# Sheet_MB.net
KiCad netlist of a schematic drawn in Altium Designer
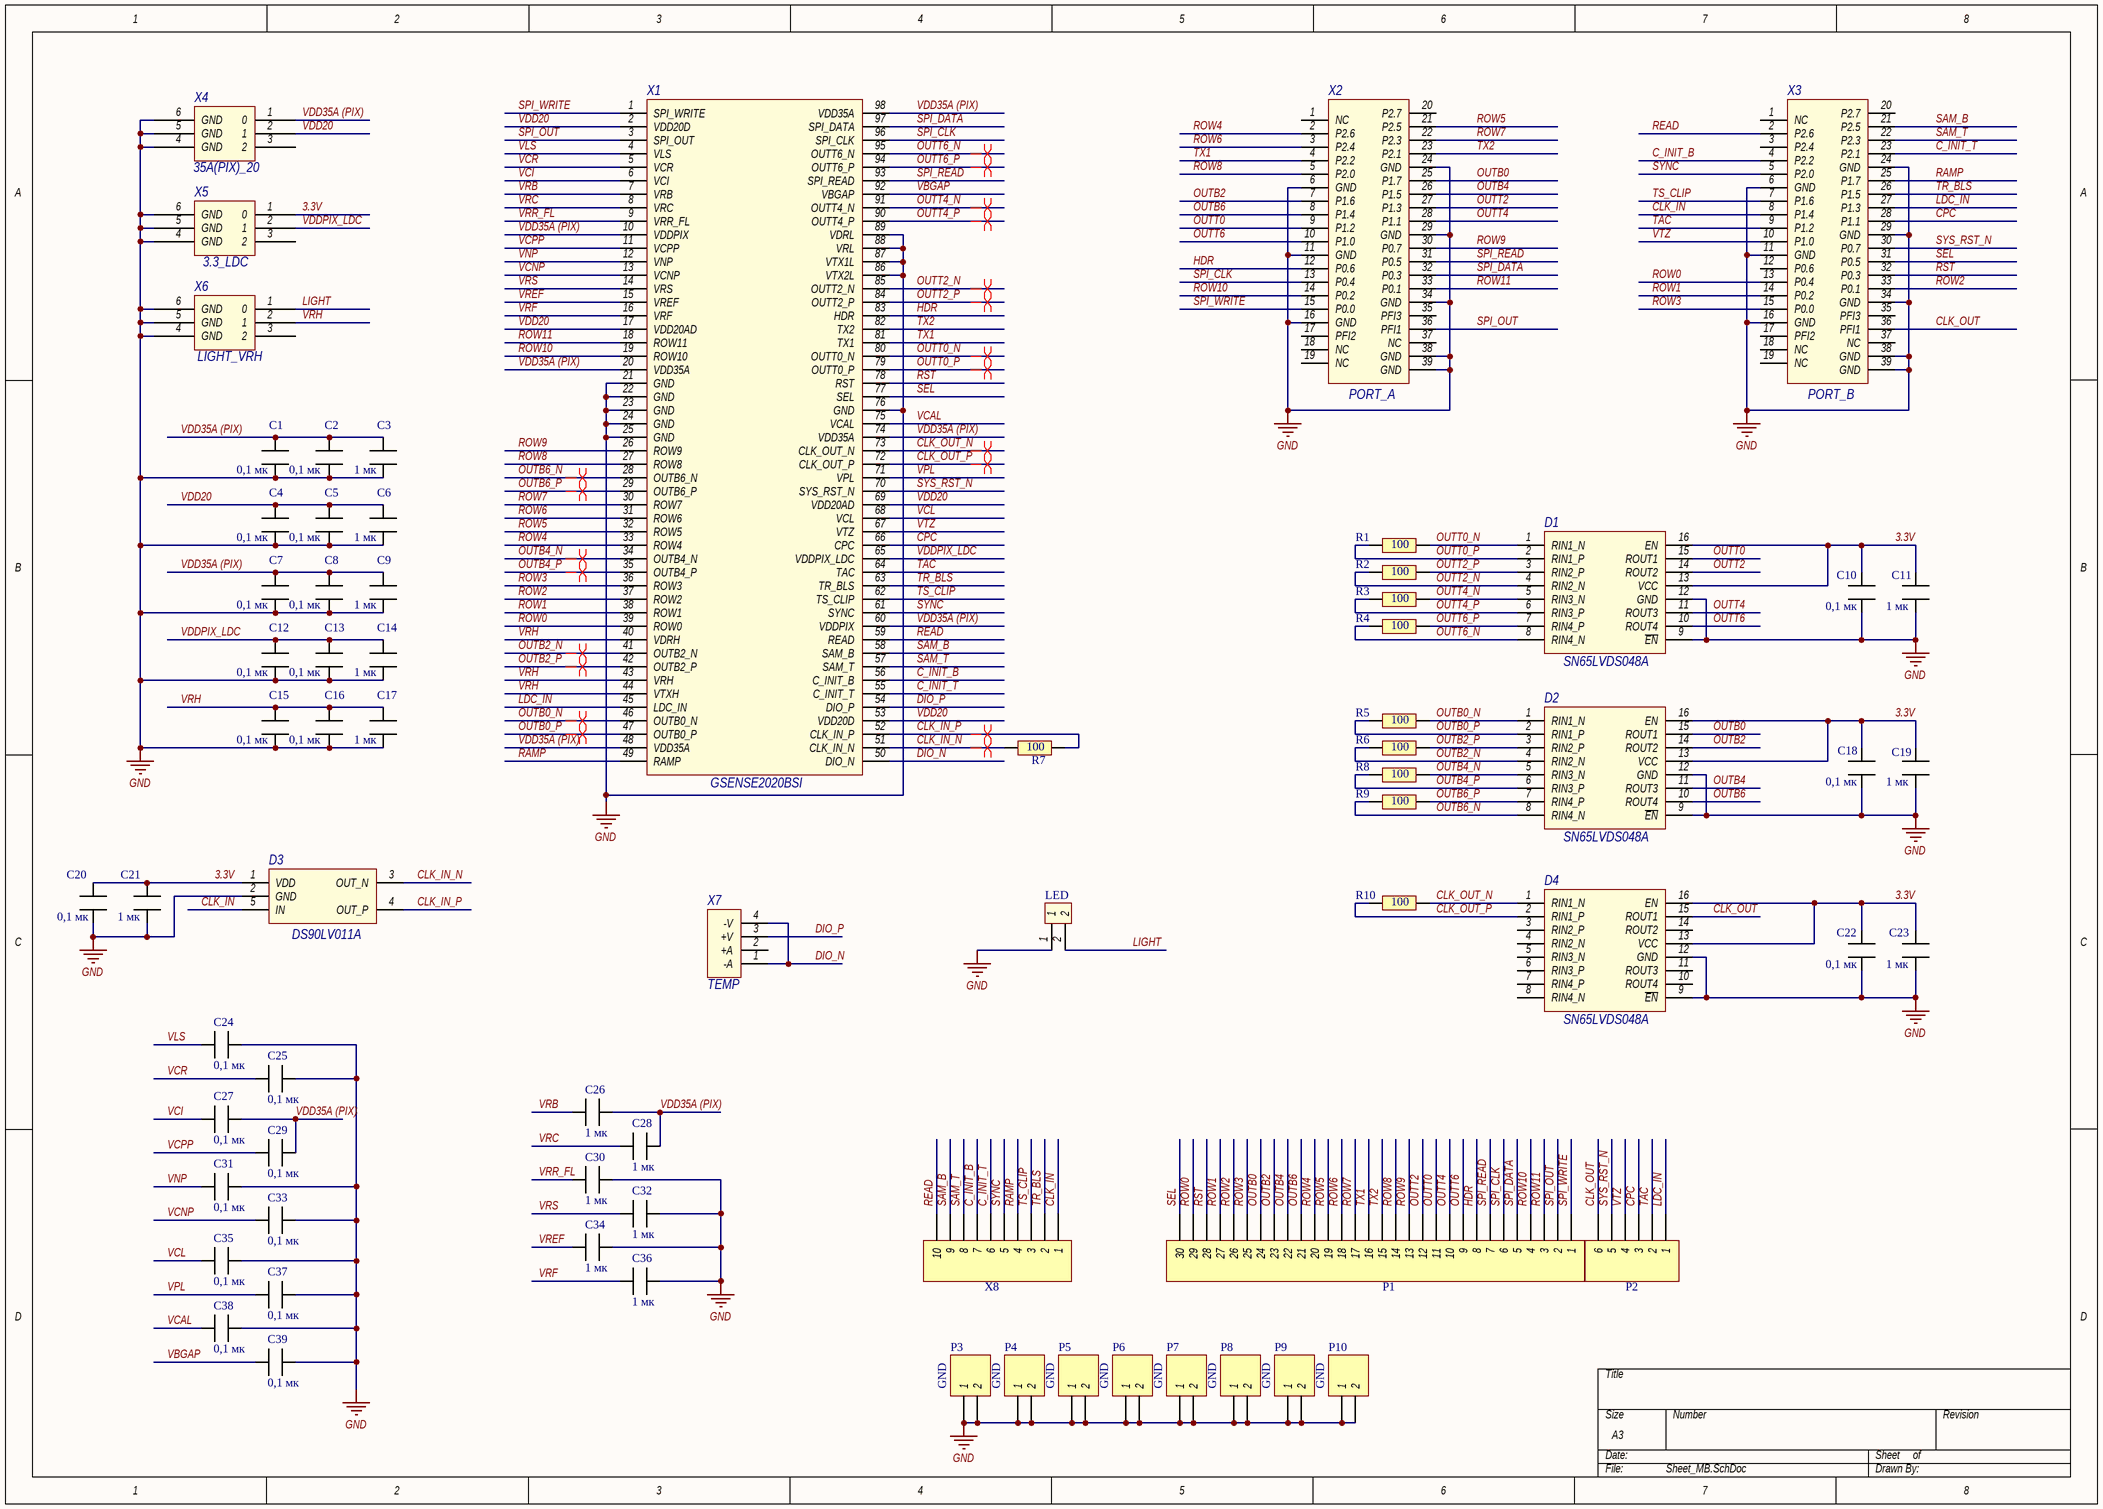
[diagram p0: Sheet_MB.SchDoc]

(export (version "E")
  (design (tool "Eeschema 10.0.6"))
  (components
    (comp (ref "C1") (value "0,1 мк") (footprint "CAP_SMALL") (libsource (lib "Schlib") (part "CAP_SMALL")))
    (comp (ref "C2") (value "0,1 мк") (footprint "CAP_SMALL") (libsource (lib "Schlib") (part "CAP_SMALL")))
    (comp (ref "C3") (value "1 мк") (footprint "CAP_SMALL") (libsource (lib "Schlib") (part "CAP_SMALL")))
    (comp (ref "C4") (value "0,1 мк") (footprint "CAP_SMALL") (libsource (lib "Schlib") (part "CAP_SMALL")))
    (comp (ref "C5") (value "0,1 мк") (footprint "CAP_SMALL") (libsource (lib "Schlib") (part "CAP_SMALL")))
    (comp (ref "C6") (value "1 мк") (footprint "CAP_SMALL") (libsource (lib "Schlib") (part "CAP_SMALL")))
    (comp (ref "C7") (value "0,1 мк") (footprint "CAP_SMALL") (libsource (lib "Schlib") (part "CAP_SMALL")))
    (comp (ref "C8") (value "0,1 мк") (footprint "CAP_SMALL") (libsource (lib "Schlib") (part "CAP_SMALL")))
    (comp (ref "C9") (value "1 мк") (footprint "CAP_SMALL") (libsource (lib "Schlib") (part "CAP_SMALL")))
    (comp (ref "C10") (value "0,1 мк") (footprint "CAP_SMALL") (libsource (lib "Schlib") (part "CAP_SMALL")))
    (comp (ref "C11") (value "1 мк") (footprint "CAP_SMALL") (libsource (lib "Schlib") (part "CAP_SMALL")))
    (comp (ref "C12") (value "0,1 мк") (footprint "CAP_SMALL") (libsource (lib "Schlib") (part "CAP_SMALL")))
    (comp (ref "C13") (value "0,1 мк") (footprint "CAP_SMALL") (libsource (lib "Schlib") (part "CAP_SMALL")))
    (comp (ref "C14") (value "1 мк") (footprint "CAP_SMALL") (libsource (lib "Schlib") (part "CAP_SMALL")))
    (comp (ref "C15") (value "0,1 мк") (footprint "CAP_SMALL") (libsource (lib "Schlib") (part "CAP_SMALL")))
    (comp (ref "C16") (value "0,1 мк") (footprint "CAP_SMALL") (libsource (lib "Schlib") (part "CAP_SMALL")))
    (comp (ref "C17") (value "1 мк") (footprint "CAP_SMALL") (libsource (lib "Schlib") (part "CAP_SMALL")))
    (comp (ref "C18") (value "0,1 мк") (footprint "CAP_SMALL") (libsource (lib "Schlib") (part "CAP_SMALL")))
    (comp (ref "C19") (value "1 мк") (footprint "CAP_SMALL") (libsource (lib "Schlib") (part "CAP_SMALL")))
    (comp (ref "C20") (value "0,1 мк") (footprint "CAP_SMALL") (libsource (lib "Schlib") (part "CAP_SMALL")))
    (comp (ref "C21") (value "1 мк") (footprint "CAP_SMALL") (libsource (lib "Schlib") (part "CAP_SMALL")))
    (comp (ref "C22") (value "0,1 мк") (footprint "CAP_SMALL") (libsource (lib "Schlib") (part "CAP_SMALL")))
    (comp (ref "C23") (value "1 мк") (footprint "CAP_SMALL") (libsource (lib "Schlib") (part "CAP_SMALL")))
    (comp (ref "C24") (value "0,1 мк") (footprint "CAP_SMALL") (libsource (lib "Schlib") (part "CAP_SMALL")))
    (comp (ref "C25") (value "0,1 мк") (footprint "CAP_SMALL") (libsource (lib "Schlib") (part "CAP_SMALL")))
    (comp (ref "C26") (value "1 мк") (footprint "CAP_SMALL") (libsource (lib "Schlib") (part "CAP_SMALL")))
    (comp (ref "C27") (value "0,1 мк") (footprint "CAP_SMALL") (libsource (lib "Schlib") (part "CAP_SMALL")))
    (comp (ref "C28") (value "1 мк") (footprint "CAP_SMALL") (libsource (lib "Schlib") (part "CAP_SMALL")))
    (comp (ref "C29") (value "0,1 мк") (footprint "CAP_SMALL") (libsource (lib "Schlib") (part "CAP_SMALL")))
    (comp (ref "C30") (value "1 мк") (footprint "CAP_SMALL") (libsource (lib "Schlib") (part "CAP_SMALL")))
    (comp (ref "C31") (value "0,1 мк") (footprint "CAP_SMALL") (libsource (lib "Schlib") (part "CAP_SMALL")))
    (comp (ref "C32") (value "1 мк") (footprint "CAP_SMALL") (libsource (lib "Schlib") (part "CAP_SMALL")))
    (comp (ref "C33") (value "0,1 мк") (footprint "CAP_SMALL") (libsource (lib "Schlib") (part "CAP_SMALL")))
    (comp (ref "C34") (value "1 мк") (footprint "CAP_SMALL") (libsource (lib "Schlib") (part "CAP_SMALL")))
    (comp (ref "C35") (value "0,1 мк") (footprint "CAP_SMALL") (libsource (lib "Schlib") (part "CAP_SMALL")))
    (comp (ref "C36") (value "1 мк") (footprint "CAP_SMALL") (libsource (lib "Schlib") (part "CAP_SMALL")))
    (comp (ref "C37") (value "0,1 мк") (footprint "CAP_SMALL") (libsource (lib "Schlib") (part "CAP_SMALL")))
    (comp (ref "C38") (value "0,1 мк") (footprint "CAP_SMALL") (libsource (lib "Schlib") (part "CAP_SMALL")))
    (comp (ref "C39") (value "0,1 мк") (footprint "CAP_SMALL") (libsource (lib "Schlib") (part "CAP_SMALL")))
    (comp (ref "D1")
      (value "SN65LVDS048A")
      (footprint "SN65LVDS048A (4LVDS)")
      (libsource (lib "Schlib") (part "SN65LVDS048A (4LVDS)"))
    )
    (comp (ref "D2")
      (value "SN65LVDS048A")
      (footprint "SN65LVDS048A (4LVDS)")
      (libsource (lib "Schlib") (part "SN65LVDS048A (4LVDS)"))
    )
    (comp (ref "D3")
      (value "DS90LV011A")
      (footprint "DS90LV011A")
      (description "LVDS Driver 1 ch")
      (libsource (lib "Schlib") (part "DS90LV011A"))
    )
    (comp (ref "D4")
      (value "SN65LVDS048A")
      (footprint "SN65LVDS048A (4LVDS)")
      (libsource (lib "Schlib") (part "SN65LVDS048A (4LVDS)"))
    )
    (comp (ref "LED") (value "LED") (footprint "KLEMMNIK_2") (libsource (lib "Schlib") (part "KLEMMNIK_2")))
    (comp (ref "P1")
      (value "Header 30")
      (footprint "HDR1X30")
      (description "Header, 30-Pin")
      (fields (field (name "PUBLISHER") "Altium Limited"))
      (libsource (lib "Miscellaneous Connectors") (part "Header 30"))
    )
    (comp (ref "P2")
      (value "Header 6")
      (footprint "HDR1X6")
      (description "Header, 6-Pin")
      (fields (field (name "PUBLISHER") "Altium Limited"))
      (libsource (lib "Miscellaneous Connectors") (part "Header 6"))
    )
    (comp (ref "P3")
      (value "GND")
      (footprint "HDR1X2")
      (description "Header, 2-Pin")
      (fields (field (name "PUBLISHER") "Altium Limited"))
      (libsource (lib "Miscellaneous Connectors") (part "Header 2"))
    )
    (comp (ref "P4")
      (value "GND")
      (footprint "HDR1X2")
      (description "Header, 2-Pin")
      (fields (field (name "PUBLISHER") "Altium Limited"))
      (libsource (lib "Miscellaneous Connectors") (part "Header 2"))
    )
    (comp (ref "P5")
      (value "GND")
      (footprint "HDR1X2")
      (description "Header, 2-Pin")
      (fields (field (name "PUBLISHER") "Altium Limited"))
      (libsource (lib "Miscellaneous Connectors") (part "Header 2"))
    )
    (comp (ref "P6")
      (value "GND")
      (footprint "HDR1X2")
      (description "Header, 2-Pin")
      (fields (field (name "PUBLISHER") "Altium Limited"))
      (libsource (lib "Miscellaneous Connectors") (part "Header 2"))
    )
    (comp (ref "P7")
      (value "GND")
      (footprint "HDR1X2")
      (description "Header, 2-Pin")
      (fields (field (name "PUBLISHER") "Altium Limited"))
      (libsource (lib "Miscellaneous Connectors") (part "Header 2"))
    )
    (comp (ref "P8")
      (value "GND")
      (footprint "HDR1X2")
      (description "Header, 2-Pin")
      (fields (field (name "PUBLISHER") "Altium Limited"))
      (libsource (lib "Miscellaneous Connectors") (part "Header 2"))
    )
    (comp (ref "P9")
      (value "GND")
      (footprint "HDR1X2")
      (description "Header, 2-Pin")
      (fields (field (name "PUBLISHER") "Altium Limited"))
      (libsource (lib "Miscellaneous Connectors") (part "Header 2"))
    )
    (comp (ref "P10")
      (value "GND")
      (footprint "HDR1X2")
      (description "Header, 2-Pin")
      (fields (field (name "PUBLISHER") "Altium Limited"))
      (libsource (lib "Miscellaneous Connectors") (part "Header 2"))
    )
    (comp (ref "R1") (value "100") (footprint "RES") (libsource (lib "Schlib") (part "RES")))
    (comp (ref "R2") (value "100") (footprint "RES") (libsource (lib "Schlib") (part "RES")))
    (comp (ref "R3") (value "100") (footprint "RES") (libsource (lib "Schlib") (part "RES")))
    (comp (ref "R4") (value "100") (footprint "RES") (libsource (lib "Schlib") (part "RES")))
    (comp (ref "R5") (value "100") (footprint "RES") (libsource (lib "Schlib") (part "RES")))
    (comp (ref "R6") (value "100") (footprint "RES") (libsource (lib "Schlib") (part "RES")))
    (comp (ref "R7") (value "100") (footprint "RES") (libsource (lib "Schlib") (part "RES")))
    (comp (ref "R8") (value "100") (footprint "RES") (libsource (lib "Schlib") (part "RES")))
    (comp (ref "R9") (value "100") (footprint "RES") (libsource (lib "Schlib") (part "RES")))
    (comp (ref "R10") (value "100") (footprint "RES") (libsource (lib "Schlib") (part "RES")))
    (comp (ref "X1")
      (value "GSENSE2020BSI")
      (footprint "GSENSE2020BSI_MEZ")
      (libsource (lib "Schlib") (part "GSENSE2020BSI_MEZ"))
    )
    (comp (ref "X2")
      (value "PORT_A")
      (footprint "CHEAP_CONN_FEMALE")
      (libsource (lib "Schlib") (part "CHEAP_CON_37_FEMALE"))
    )
    (comp (ref "X3")
      (value "PORT_B")
      (footprint "CHEAP_CONN_FEMALE")
      (libsource (lib "Schlib") (part "CHEAP_CON_37_FEMALE"))
    )
    (comp (ref "X4") (value "35A(PIX)_20") (footprint "POWER") (libsource (lib "Schlib") (part "POWER")))
    (comp (ref "X5") (value "3.3_LDC") (footprint "POWER") (libsource (lib "Schlib") (part "POWER")))
    (comp (ref "X6") (value "LIGHT_VRH") (footprint "POWER") (libsource (lib "Schlib") (part "POWER")))
    (comp (ref "X7")
      (value "TEMP")
      (footprint "AMP_VOLTMETER")
      (libsource (lib "Schlib") (part "AMP_VOLTMETER"))
    )
    (comp (ref "X8")
      (value "Header 10")
      (footprint "HDR1X10")
      (description "Header, 10-Pin")
      (fields (field (name "PUBLISHER") "Altium Limited"))
      (libsource (lib "Miscellaneous Connectors") (part "Header 10"))
    )
  )
  (nets
    (net (code "1") (name "/3.3V") (class "Default")
      (node (ref "C10") (pin "2") (pinfunction "2_2") (pintype "passive"))
      (node (ref "C11") (pin "2") (pinfunction "2_2") (pintype "passive"))
      (node (ref "C18") (pin "2") (pinfunction "2_2") (pintype "passive"))
      (node (ref "C19") (pin "2") (pinfunction "2_2") (pintype "passive"))
      (node (ref "C20") (pin "2") (pinfunction "2_2") (pintype "passive"))
      (node (ref "C21") (pin "2") (pinfunction "2_2") (pintype "passive"))
      (node (ref "C22") (pin "2") (pinfunction "2_2") (pintype "passive"))
      (node (ref "C23") (pin "2") (pinfunction "2_2") (pintype "passive"))
      (node (ref "D1") (pin "13") (pinfunction "VCC_13") (pintype "passive"))
      (node (ref "D1") (pin "16") (pinfunction "EN_16") (pintype "passive"))
      (node (ref "D2") (pin "13") (pinfunction "VCC_13") (pintype "passive"))
      (node (ref "D2") (pin "16") (pinfunction "EN_16") (pintype "passive"))
      (node (ref "D3") (pin "1") (pinfunction "VDD_1") (pintype "passive"))
      (node (ref "D4") (pin "13") (pinfunction "VCC_13") (pintype "passive"))
      (node (ref "D4") (pin "16") (pinfunction "EN_16") (pintype "passive"))
      (node (ref "X5") (pin "1") (pinfunction "0_1") (pintype "passive"))
    )
    (net (code "2") (name "/CLK_IN") (class "Default")
      (node (ref "D3") (pin "5") (pinfunction "IN_5") (pintype "passive"))
      (node (ref "X3") (pin "8") (pinfunction "P1.4_8") (pintype "passive"))
      (node (ref "X8") (pin "1") (pinfunction "1_1") (pintype "passive"))
    )
    (net (code "3") (name "/CLK_IN_N") (class "Default")
      (node (ref "D3") (pin "3") (pinfunction "OUT_N_3") (pintype "passive"))
      (node (ref "R7") (pin "1") (pinfunction "1_1") (pintype "passive"))
      (node (ref "X1") (pin "51") (pinfunction "CLK_IN_N_51") (pintype "passive"))
    )
    (net (code "4") (name "/CLK_IN_P") (class "Default")
      (node (ref "D3") (pin "4") (pinfunction "OUT_P_4") (pintype "passive"))
      (node (ref "R7") (pin "2") (pinfunction "2_2") (pintype "passive"))
      (node (ref "X1") (pin "52") (pinfunction "CLK_IN_P_52") (pintype "passive"))
    )
    (net (code "5") (name "/CLK_OUT") (class "Default")
      (node (ref "D4") (pin "15") (pinfunction "ROUT1_15") (pintype "passive"))
      (node (ref "P2") (pin "6") (pinfunction "6_6") (pintype "passive"))
      (node (ref "X3") (pin "36") (pinfunction "PFI1_36") (pintype "passive"))
    )
    (net (code "6") (name "/CLK_OUT_N") (class "Default")
      (node (ref "D4") (pin "1") (pinfunction "RIN1_N_1") (pintype "passive"))
      (node (ref "R10") (pin "2") (pinfunction "2_2") (pintype "passive"))
      (node (ref "X1") (pin "73") (pinfunction "CLK_OUT_N_73") (pintype "passive"))
    )
    (net (code "7") (name "/CLK_OUT_P") (class "Default")
      (node (ref "D4") (pin "2") (pinfunction "RIN1_P_2") (pintype "passive"))
      (node (ref "R10") (pin "1") (pinfunction "1_1") (pintype "passive"))
      (node (ref "X1") (pin "72") (pinfunction "CLK_OUT_P_72") (pintype "passive"))
    )
    (net (code "8") (name "/CPC") (class "Default")
      (node (ref "P2") (pin "3") (pinfunction "3_3") (pintype "passive"))
      (node (ref "X1") (pin "66") (pinfunction "CPC_66") (pintype "passive"))
      (node (ref "X3") (pin "28") (pinfunction "P1.1_28") (pintype "passive"))
    )
    (net (code "9") (name "/C_INIT_B") (class "Default")
      (node (ref "X1") (pin "56") (pinfunction "C_INIT_B_56") (pintype "passive"))
      (node (ref "X3") (pin "4") (pinfunction "P2.2_4") (pintype "passive"))
      (node (ref "X8") (pin "7") (pinfunction "7_7") (pintype "passive"))
    )
    (net (code "10") (name "/C_INIT_T") (class "Default")
      (node (ref "X1") (pin "55") (pinfunction "C_INIT_T_55") (pintype "passive"))
      (node (ref "X3") (pin "23") (pinfunction "P2.1_23") (pintype "passive"))
      (node (ref "X8") (pin "6") (pinfunction "6_6") (pintype "passive"))
    )
    (net (code "11") (name "/DIO_N") (class "Default")
      (node (ref "X1") (pin "50") (pinfunction "DIO_N_50") (pintype "passive"))
      (node (ref "X7") (pin "1") (pinfunction "-A_1") (pintype "passive"))
      (node (ref "X7") (pin "4") (pinfunction "-V_4") (pintype "passive"))
    )
    (net (code "12") (name "/DIO_P") (class "Default")
      (node (ref "X1") (pin "54") (pinfunction "DIO_P_54") (pintype "passive"))
      (node (ref "X7") (pin "3") (pinfunction "+V_3") (pintype "passive"))
    )
    (net (code "13") (name "/HDR") (class "Default")
      (node (ref "P1") (pin "8") (pinfunction "8_8") (pintype "passive"))
      (node (ref "X1") (pin "83") (pinfunction "HDR_83") (pintype "passive"))
      (node (ref "X2") (pin "12") (pinfunction "P0.6_12") (pintype "passive"))
    )
    (net (code "14") (name "/LDC_IN") (class "Default")
      (node (ref "P2") (pin "1") (pinfunction "1_1") (pintype "passive"))
      (node (ref "X1") (pin "45") (pinfunction "LDC_IN_45") (pintype "passive"))
      (node (ref "X3") (pin "27") (pinfunction "P1.3_27") (pintype "passive"))
    )
    (net (code "15") (name "/LIGHT") (class "Default")
      (node (ref "LED") (pin "2") (pinfunction "2_2") (pintype "passive"))
      (node (ref "X6") (pin "1") (pinfunction "0_1") (pintype "passive"))
    )
    (net (code "16") (name "/OUTB0") (class "Default")
      (node (ref "D2") (pin "15") (pinfunction "ROUT1_15") (pintype "passive"))
      (node (ref "P1") (pin "24") (pinfunction "24_24") (pintype "passive"))
      (node (ref "X2") (pin "25") (pinfunction "P1.7_25") (pintype "passive"))
    )
    (net (code "17") (name "/OUTB0_N") (class "Default")
      (node (ref "D2") (pin "1") (pinfunction "RIN1_N_1") (pintype "passive"))
      (node (ref "R5") (pin "2") (pinfunction "2_2") (pintype "passive"))
      (node (ref "X1") (pin "46") (pinfunction "OUTB0_N_46") (pintype "passive"))
    )
    (net (code "18") (name "/OUTB0_P") (class "Default")
      (node (ref "D2") (pin "2") (pinfunction "RIN1_P_2") (pintype "passive"))
      (node (ref "R5") (pin "1") (pinfunction "1_1") (pintype "passive"))
      (node (ref "X1") (pin "47") (pinfunction "OUTB0_P_47") (pintype "passive"))
    )
    (net (code "19") (name "/OUTB2") (class "Default")
      (node (ref "D2") (pin "14") (pinfunction "ROUT2_14") (pintype "passive"))
      (node (ref "P1") (pin "23") (pinfunction "23_23") (pintype "passive"))
      (node (ref "X2") (pin "7") (pinfunction "P1.6_7") (pintype "passive"))
    )
    (net (code "20") (name "/OUTB2_N") (class "Default")
      (node (ref "D2") (pin "4") (pinfunction "RIN2_N_4") (pintype "passive"))
      (node (ref "R6") (pin "1") (pinfunction "1_1") (pintype "passive"))
      (node (ref "X1") (pin "41") (pinfunction "OUTB2_N_41") (pintype "passive"))
    )
    (net (code "21") (name "/OUTB2_P") (class "Default")
      (node (ref "D2") (pin "3") (pinfunction "RIN2_P_3") (pintype "passive"))
      (node (ref "R6") (pin "2") (pinfunction "2_2") (pintype "passive"))
      (node (ref "X1") (pin "42") (pinfunction "OUTB2_P_42") (pintype "passive"))
    )
    (net (code "22") (name "/OUTB4") (class "Default")
      (node (ref "D2") (pin "11") (pinfunction "ROUT3_11") (pintype "passive"))
      (node (ref "P1") (pin "22") (pinfunction "22_22") (pintype "passive"))
      (node (ref "X2") (pin "26") (pinfunction "P1.5_26") (pintype "passive"))
    )
    (net (code "23") (name "/OUTB4_N") (class "Default")
      (node (ref "D2") (pin "5") (pinfunction "RIN3_N_5") (pintype "passive"))
      (node (ref "R8") (pin "2") (pinfunction "2_2") (pintype "passive"))
      (node (ref "X1") (pin "34") (pinfunction "OUTB4_N_34") (pintype "passive"))
    )
    (net (code "24") (name "/OUTB4_P") (class "Default")
      (node (ref "D2") (pin "6") (pinfunction "RIN3_P_6") (pintype "passive"))
      (node (ref "R8") (pin "1") (pinfunction "1_1") (pintype "passive"))
      (node (ref "X1") (pin "35") (pinfunction "OUTB4_P_35") (pintype "passive"))
    )
    (net (code "25") (name "/OUTB6") (class "Default")
      (node (ref "D2") (pin "10") (pinfunction "ROUT4_10") (pintype "passive"))
      (node (ref "P1") (pin "21") (pinfunction "21_21") (pintype "passive"))
      (node (ref "X2") (pin "8") (pinfunction "P1.4_8") (pintype "passive"))
    )
    (net (code "26") (name "/OUTB6_N") (class "Default")
      (node (ref "D2") (pin "8") (pinfunction "RIN4_N_8") (pintype "passive"))
      (node (ref "R9") (pin "1") (pinfunction "1_1") (pintype "passive"))
      (node (ref "X1") (pin "28") (pinfunction "OUTB6_N_28") (pintype "passive"))
    )
    (net (code "27") (name "/OUTB6_P") (class "Default")
      (node (ref "D2") (pin "7") (pinfunction "RIN4_P_7") (pintype "passive"))
      (node (ref "R9") (pin "2") (pinfunction "2_2") (pintype "passive"))
      (node (ref "X1") (pin "29") (pinfunction "OUTB6_P_29") (pintype "passive"))
    )
    (net (code "28") (name "/OUTT0") (class "Default")
      (node (ref "D1") (pin "15") (pinfunction "ROUT1_15") (pintype "passive"))
      (node (ref "P1") (pin "11") (pinfunction "11_11") (pintype "passive"))
      (node (ref "X2") (pin "9") (pinfunction "P1.2_9") (pintype "passive"))
    )
    (net (code "29") (name "/OUTT0_N") (class "Default")
      (node (ref "D1") (pin "1") (pinfunction "RIN1_N_1") (pintype "passive"))
      (node (ref "R1") (pin "2") (pinfunction "2_2") (pintype "passive"))
      (node (ref "X1") (pin "80") (pinfunction "OUTT0_N_80") (pintype "passive"))
    )
    (net (code "30") (name "/OUTT0_P") (class "Default")
      (node (ref "D1") (pin "2") (pinfunction "RIN1_P_2") (pintype "passive"))
      (node (ref "R1") (pin "1") (pinfunction "1_1") (pintype "passive"))
      (node (ref "X1") (pin "79") (pinfunction "OUTT0_P_79") (pintype "passive"))
    )
    (net (code "31") (name "/OUTT2") (class "Default")
      (node (ref "D1") (pin "14") (pinfunction "ROUT2_14") (pintype "passive"))
      (node (ref "P1") (pin "12") (pinfunction "12_12") (pintype "passive"))
      (node (ref "X2") (pin "27") (pinfunction "P1.3_27") (pintype "passive"))
    )
    (net (code "32") (name "/OUTT2_N") (class "Default")
      (node (ref "D1") (pin "4") (pinfunction "RIN2_N_4") (pintype "passive"))
      (node (ref "R2") (pin "1") (pinfunction "1_1") (pintype "passive"))
      (node (ref "X1") (pin "85") (pinfunction "OUTT2_N_85") (pintype "passive"))
    )
    (net (code "33") (name "/OUTT2_P") (class "Default")
      (node (ref "D1") (pin "3") (pinfunction "RIN2_P_3") (pintype "passive"))
      (node (ref "R2") (pin "2") (pinfunction "2_2") (pintype "passive"))
      (node (ref "X1") (pin "84") (pinfunction "OUTT2_P_84") (pintype "passive"))
    )
    (net (code "34") (name "/OUTT4") (class "Default")
      (node (ref "D1") (pin "11") (pinfunction "ROUT3_11") (pintype "passive"))
      (node (ref "P1") (pin "10") (pinfunction "10_10") (pintype "passive"))
      (node (ref "X2") (pin "28") (pinfunction "P1.1_28") (pintype "passive"))
    )
    (net (code "35") (name "/OUTT4_N") (class "Default")
      (node (ref "D1") (pin "5") (pinfunction "RIN3_N_5") (pintype "passive"))
      (node (ref "R3") (pin "2") (pinfunction "2_2") (pintype "passive"))
      (node (ref "X1") (pin "91") (pinfunction "OUTT4_N_91") (pintype "passive"))
    )
    (net (code "36") (name "/OUTT4_P") (class "Default")
      (node (ref "D1") (pin "6") (pinfunction "RIN3_P_6") (pintype "passive"))
      (node (ref "R3") (pin "1") (pinfunction "1_1") (pintype "passive"))
      (node (ref "X1") (pin "90") (pinfunction "OUTT4_P_90") (pintype "passive"))
    )
    (net (code "37") (name "/OUTT6") (class "Default")
      (node (ref "D1") (pin "10") (pinfunction "ROUT4_10") (pintype "passive"))
      (node (ref "P1") (pin "9") (pinfunction "9_9") (pintype "passive"))
      (node (ref "X2") (pin "10") (pinfunction "P1.0_10") (pintype "passive"))
    )
    (net (code "38") (name "/OUTT6_N") (class "Default")
      (node (ref "D1") (pin "8") (pinfunction "RIN4_N_8") (pintype "passive"))
      (node (ref "R4") (pin "1") (pinfunction "1_1") (pintype "passive"))
      (node (ref "X1") (pin "95") (pinfunction "OUTT6_N_95") (pintype "passive"))
    )
    (net (code "39") (name "/OUTT6_P") (class "Default")
      (node (ref "D1") (pin "7") (pinfunction "RIN4_P_7") (pintype "passive"))
      (node (ref "R4") (pin "2") (pinfunction "2_2") (pintype "passive"))
      (node (ref "X1") (pin "94") (pinfunction "OUTT6_P_94") (pintype "passive"))
    )
    (net (code "40") (name "/RAMP") (class "Default")
      (node (ref "X1") (pin "49") (pinfunction "RAMP_49") (pintype "passive"))
      (node (ref "X3") (pin "25") (pinfunction "P1.7_25") (pintype "passive"))
      (node (ref "X8") (pin "4") (pinfunction "4_4") (pintype "passive"))
    )
    (net (code "41") (name "/READ") (class "Default")
      (node (ref "X1") (pin "59") (pinfunction "READ_59") (pintype "passive"))
      (node (ref "X3") (pin "2") (pinfunction "P2.6_2") (pintype "passive"))
      (node (ref "X8") (pin "10") (pinfunction "10_10") (pintype "passive"))
    )
    (net (code "42") (name "/ROW0") (class "Default")
      (node (ref "P1") (pin "29") (pinfunction "29_29") (pintype "passive"))
      (node (ref "X1") (pin "39") (pinfunction "ROW0_39") (pintype "passive"))
      (node (ref "X3") (pin "13") (pinfunction "P0.4_13") (pintype "passive"))
    )
    (net (code "43") (name "/ROW1") (class "Default")
      (node (ref "P1") (pin "27") (pinfunction "27_27") (pintype "passive"))
      (node (ref "X1") (pin "38") (pinfunction "ROW1_38") (pintype "passive"))
      (node (ref "X3") (pin "14") (pinfunction "P0.2_14") (pintype "passive"))
    )
    (net (code "44") (name "/ROW2") (class "Default")
      (node (ref "P1") (pin "26") (pinfunction "26_26") (pintype "passive"))
      (node (ref "X1") (pin "37") (pinfunction "ROW2_37") (pintype "passive"))
      (node (ref "X3") (pin "33") (pinfunction "P0.1_33") (pintype "passive"))
    )
    (net (code "45") (name "/ROW3") (class "Default")
      (node (ref "P1") (pin "25") (pinfunction "25_25") (pintype "passive"))
      (node (ref "X1") (pin "36") (pinfunction "ROW3_36") (pintype "passive"))
      (node (ref "X3") (pin "15") (pinfunction "P0.0_15") (pintype "passive"))
    )
    (net (code "46") (name "/ROW4") (class "Default")
      (node (ref "P1") (pin "20") (pinfunction "20_20") (pintype "passive"))
      (node (ref "X1") (pin "33") (pinfunction "ROW4_33") (pintype "passive"))
      (node (ref "X2") (pin "2") (pinfunction "P2.6_2") (pintype "passive"))
    )
    (net (code "47") (name "/ROW5") (class "Default")
      (node (ref "P1") (pin "19") (pinfunction "19_19") (pintype "passive"))
      (node (ref "X1") (pin "32") (pinfunction "ROW5_32") (pintype "passive"))
      (node (ref "X2") (pin "21") (pinfunction "P2.5_21") (pintype "passive"))
    )
    (net (code "48") (name "/ROW6") (class "Default")
      (node (ref "P1") (pin "18") (pinfunction "18_18") (pintype "passive"))
      (node (ref "X1") (pin "31") (pinfunction "ROW6_31") (pintype "passive"))
      (node (ref "X2") (pin "3") (pinfunction "P2.4_3") (pintype "passive"))
    )
    (net (code "49") (name "/ROW7") (class "Default")
      (node (ref "P1") (pin "17") (pinfunction "17_17") (pintype "passive"))
      (node (ref "X1") (pin "30") (pinfunction "ROW7_30") (pintype "passive"))
      (node (ref "X2") (pin "22") (pinfunction "P2.3_22") (pintype "passive"))
    )
    (net (code "50") (name "/ROW8") (class "Default")
      (node (ref "P1") (pin "14") (pinfunction "14_14") (pintype "passive"))
      (node (ref "X1") (pin "27") (pinfunction "ROW8_27") (pintype "passive"))
      (node (ref "X2") (pin "5") (pinfunction "P2.0_5") (pintype "passive"))
    )
    (net (code "51") (name "/ROW9") (class "Default")
      (node (ref "P1") (pin "13") (pinfunction "13_13") (pintype "passive"))
      (node (ref "X1") (pin "26") (pinfunction "ROW9_26") (pintype "passive"))
      (node (ref "X2") (pin "30") (pinfunction "P0.7_30") (pintype "passive"))
    )
    (net (code "52") (name "/ROW10") (class "Default")
      (node (ref "P1") (pin "4") (pinfunction "4_4") (pintype "passive"))
      (node (ref "X1") (pin "19") (pinfunction "ROW10_19") (pintype "passive"))
      (node (ref "X2") (pin "14") (pinfunction "P0.2_14") (pintype "passive"))
    )
    (net (code "53") (name "/ROW11") (class "Default")
      (node (ref "P1") (pin "3") (pinfunction "3_3") (pintype "passive"))
      (node (ref "X1") (pin "18") (pinfunction "ROW11_18") (pintype "passive"))
      (node (ref "X2") (pin "33") (pinfunction "P0.1_33") (pintype "passive"))
    )
    (net (code "54") (name "/RST") (class "Default")
      (node (ref "P1") (pin "28") (pinfunction "28_28") (pintype "passive"))
      (node (ref "X1") (pin "78") (pinfunction "RST_78") (pintype "passive"))
      (node (ref "X3") (pin "32") (pinfunction "P0.3_32") (pintype "passive"))
    )
    (net (code "55") (name "/SAM_B") (class "Default")
      (node (ref "X1") (pin "58") (pinfunction "SAM_B_58") (pintype "passive"))
      (node (ref "X3") (pin "21") (pinfunction "P2.5_21") (pintype "passive"))
      (node (ref "X8") (pin "9") (pinfunction "9_9") (pintype "passive"))
    )
    (net (code "56") (name "/SAM_T") (class "Default")
      (node (ref "X1") (pin "57") (pinfunction "SAM_T_57") (pintype "passive"))
      (node (ref "X3") (pin "22") (pinfunction "P2.3_22") (pintype "passive"))
      (node (ref "X8") (pin "8") (pinfunction "8_8") (pintype "passive"))
    )
    (net (code "57") (name "/SEL") (class "Default")
      (node (ref "P1") (pin "30") (pinfunction "30_30") (pintype "passive"))
      (node (ref "X1") (pin "77") (pinfunction "SEL_77") (pintype "passive"))
      (node (ref "X3") (pin "31") (pinfunction "P0.5_31") (pintype "passive"))
    )
    (net (code "58") (name "/SPI_CLK") (class "Default")
      (node (ref "P1") (pin "6") (pinfunction "6_6") (pintype "passive"))
      (node (ref "X1") (pin "96") (pinfunction "SPI_CLK_96") (pintype "passive"))
      (node (ref "X2") (pin "13") (pinfunction "P0.4_13") (pintype "passive"))
    )
    (net (code "59") (name "/SPI_DATA") (class "Default")
      (node (ref "P1") (pin "5") (pinfunction "5_5") (pintype "passive"))
      (node (ref "X1") (pin "97") (pinfunction "SPI_DATA_97") (pintype "passive"))
      (node (ref "X2") (pin "32") (pinfunction "P0.3_32") (pintype "passive"))
    )
    (net (code "60") (name "/SPI_OUT") (class "Default")
      (node (ref "P1") (pin "2") (pinfunction "2_2") (pintype "passive"))
      (node (ref "X1") (pin "3") (pinfunction "SPI_OUT_3") (pintype "passive"))
      (node (ref "X2") (pin "36") (pinfunction "PFI1_36") (pintype "passive"))
    )
    (net (code "61") (name "/SPI_READ") (class "Default")
      (node (ref "P1") (pin "7") (pinfunction "7_7") (pintype "passive"))
      (node (ref "X1") (pin "93") (pinfunction "SPI_READ_93") (pintype "passive"))
      (node (ref "X2") (pin "31") (pinfunction "P0.5_31") (pintype "passive"))
    )
    (net (code "62") (name "/SPI_WRITE") (class "Default")
      (node (ref "P1") (pin "1") (pinfunction "1_1") (pintype "passive"))
      (node (ref "X1") (pin "1") (pinfunction "SPI_WRITE_1") (pintype "passive"))
      (node (ref "X2") (pin "15") (pinfunction "P0.0_15") (pintype "passive"))
    )
    (net (code "63") (name "/SYNC") (class "Default")
      (node (ref "X1") (pin "61") (pinfunction "SYNC_61") (pintype "passive"))
      (node (ref "X3") (pin "5") (pinfunction "P2.0_5") (pintype "passive"))
      (node (ref "X8") (pin "5") (pinfunction "5_5") (pintype "passive"))
    )
    (net (code "64") (name "/SYS_RST_N") (class "Default")
      (node (ref "P2") (pin "5") (pinfunction "5_5") (pintype "passive"))
      (node (ref "X1") (pin "70") (pinfunction "SYS_RST_N_70") (pintype "passive"))
      (node (ref "X3") (pin "30") (pinfunction "P0.7_30") (pintype "passive"))
    )
    (net (code "65") (name "/TAC") (class "Default")
      (node (ref "P2") (pin "2") (pinfunction "2_2") (pintype "passive"))
      (node (ref "X1") (pin "64") (pinfunction "TAC_64") (pintype "passive"))
      (node (ref "X3") (pin "9") (pinfunction "P1.2_9") (pintype "passive"))
    )
    (net (code "66") (name "/TR_BLS") (class "Default")
      (node (ref "X1") (pin "63") (pinfunction "TR_BLS_63") (pintype "passive"))
      (node (ref "X3") (pin "26") (pinfunction "P1.5_26") (pintype "passive"))
      (node (ref "X8") (pin "2") (pinfunction "2_2") (pintype "passive"))
    )
    (net (code "67") (name "/TS_CLIP") (class "Default")
      (node (ref "X1") (pin "62") (pinfunction "TS_CLIP_62") (pintype "passive"))
      (node (ref "X3") (pin "7") (pinfunction "P1.6_7") (pintype "passive"))
      (node (ref "X8") (pin "3") (pinfunction "3_3") (pintype "passive"))
    )
    (net (code "68") (name "/TX1") (class "Default")
      (node (ref "P1") (pin "16") (pinfunction "16_16") (pintype "passive"))
      (node (ref "X1") (pin "81") (pinfunction "TX1_81") (pintype "passive"))
      (node (ref "X2") (pin "4") (pinfunction "P2.2_4") (pintype "passive"))
    )
    (net (code "69") (name "/TX2") (class "Default")
      (node (ref "P1") (pin "15") (pinfunction "15_15") (pintype "passive"))
      (node (ref "X1") (pin "82") (pinfunction "TX2_82") (pintype "passive"))
      (node (ref "X2") (pin "23") (pinfunction "P2.1_23") (pintype "passive"))
    )
    (net (code "70") (name "/VBGAP") (class "Default")
      (node (ref "C39") (pin "2") (pinfunction "2_2") (pintype "passive"))
      (node (ref "X1") (pin "92") (pinfunction "VBGAP_92") (pintype "passive"))
    )
    (net (code "71") (name "/VCAL") (class "Default")
      (node (ref "C38") (pin "2") (pinfunction "2_2") (pintype "passive"))
      (node (ref "X1") (pin "75") (pinfunction "VCAL_75") (pintype "passive"))
    )
    (net (code "72") (name "/VCI") (class "Default")
      (node (ref "C27") (pin "2") (pinfunction "2_2") (pintype "passive"))
      (node (ref "X1") (pin "6") (pinfunction "VCI_6") (pintype "passive"))
    )
    (net (code "73") (name "/VCL") (class "Default")
      (node (ref "C35") (pin "2") (pinfunction "2_2") (pintype "passive"))
      (node (ref "X1") (pin "68") (pinfunction "VCL_68") (pintype "passive"))
    )
    (net (code "74") (name "/VCNP") (class "Default")
      (node (ref "C33") (pin "2") (pinfunction "2_2") (pintype "passive"))
      (node (ref "X1") (pin "13") (pinfunction "VCNP_13") (pintype "passive"))
    )
    (net (code "75") (name "/VCPP") (class "Default")
      (node (ref "C29") (pin "2") (pinfunction "2_2") (pintype "passive"))
      (node (ref "X1") (pin "11") (pinfunction "VCPP_11") (pintype "passive"))
    )
    (net (code "76") (name "/VCR") (class "Default")
      (node (ref "C25") (pin "2") (pinfunction "2_2") (pintype "passive"))
      (node (ref "X1") (pin "5") (pinfunction "VCR_5") (pintype "passive"))
    )
    (net (code "77") (name "/VDD20") (class "Default")
      (node (ref "C4") (pin "2") (pinfunction "2_2") (pintype "passive"))
      (node (ref "C5") (pin "2") (pinfunction "2_2") (pintype "passive"))
      (node (ref "C6") (pin "2") (pinfunction "2_2") (pintype "passive"))
      (node (ref "X1") (pin "17") (pinfunction "VDD20AD_17") (pintype "passive"))
      (node (ref "X1") (pin "2") (pinfunction "VDD20D_2") (pintype "passive"))
      (node (ref "X1") (pin "53") (pinfunction "VDD20D_53") (pintype "passive"))
      (node (ref "X1") (pin "69") (pinfunction "VDD20AD_69") (pintype "passive"))
      (node (ref "X4") (pin "2") (pinfunction "1_2") (pintype "passive"))
    )
    (net (code "78") (name "/VDD35A (PIX)") (class "Default")
      (node (ref "C1") (pin "2") (pinfunction "2_2") (pintype "passive"))
      (node (ref "C2") (pin "2") (pinfunction "2_2") (pintype "passive"))
      (node (ref "C26") (pin "1") (pinfunction "1_1") (pintype "passive"))
      (node (ref "C27") (pin "1") (pinfunction "1_1") (pintype "passive"))
      (node (ref "C28") (pin "1") (pinfunction "1_1") (pintype "passive"))
      (node (ref "C29") (pin "1") (pinfunction "1_1") (pintype "passive"))
      (node (ref "C3") (pin "2") (pinfunction "2_2") (pintype "passive"))
      (node (ref "C7") (pin "2") (pinfunction "2_2") (pintype "passive"))
      (node (ref "C8") (pin "2") (pinfunction "2_2") (pintype "passive"))
      (node (ref "C9") (pin "2") (pinfunction "2_2") (pintype "passive"))
      (node (ref "X1") (pin "10") (pinfunction "VDDPIX_10") (pintype "passive"))
      (node (ref "X1") (pin "20") (pinfunction "VDD35A_20") (pintype "passive"))
      (node (ref "X1") (pin "48") (pinfunction "VDD35A_48") (pintype "passive"))
      (node (ref "X1") (pin "60") (pinfunction "VDDPIX_60") (pintype "passive"))
      (node (ref "X1") (pin "74") (pinfunction "VDD35A_74") (pintype "passive"))
      (node (ref "X1") (pin "98") (pinfunction "VDD35A_98") (pintype "passive"))
      (node (ref "X4") (pin "1") (pinfunction "0_1") (pintype "passive"))
    )
    (net (code "79") (name "/VDDPIX_LDC") (class "Default")
      (node (ref "C12") (pin "2") (pinfunction "2_2") (pintype "passive"))
      (node (ref "C13") (pin "2") (pinfunction "2_2") (pintype "passive"))
      (node (ref "C14") (pin "2") (pinfunction "2_2") (pintype "passive"))
      (node (ref "X1") (pin "65") (pinfunction "VDDPIX_LDC_65") (pintype "passive"))
      (node (ref "X5") (pin "2") (pinfunction "1_2") (pintype "passive"))
    )
    (net (code "80") (name "/VLS") (class "Default")
      (node (ref "C24") (pin "2") (pinfunction "2_2") (pintype "passive"))
      (node (ref "X1") (pin "4") (pinfunction "VLS_4") (pintype "passive"))
    )
    (net (code "81") (name "/VNP") (class "Default")
      (node (ref "C31") (pin "2") (pinfunction "2_2") (pintype "passive"))
      (node (ref "X1") (pin "12") (pinfunction "VNP_12") (pintype "passive"))
    )
    (net (code "82") (name "/VPL") (class "Default")
      (node (ref "C37") (pin "2") (pinfunction "2_2") (pintype "passive"))
      (node (ref "X1") (pin "71") (pinfunction "VPL_71") (pintype "passive"))
    )
    (net (code "83") (name "/VRB") (class "Default")
      (node (ref "C26") (pin "2") (pinfunction "2_2") (pintype "passive"))
      (node (ref "X1") (pin "7") (pinfunction "VRB_7") (pintype "passive"))
    )
    (net (code "84") (name "/VRC") (class "Default")
      (node (ref "C28") (pin "2") (pinfunction "2_2") (pintype "passive"))
      (node (ref "X1") (pin "8") (pinfunction "VRC_8") (pintype "passive"))
    )
    (net (code "85") (name "/VREF") (class "Default")
      (node (ref "C34") (pin "2") (pinfunction "2_2") (pintype "passive"))
      (node (ref "X1") (pin "15") (pinfunction "VREF_15") (pintype "passive"))
    )
    (net (code "86") (name "/VRF") (class "Default")
      (node (ref "C36") (pin "2") (pinfunction "2_2") (pintype "passive"))
      (node (ref "X1") (pin "16") (pinfunction "VRF_16") (pintype "passive"))
    )
    (net (code "87") (name "/VRH") (class "Default")
      (node (ref "C15") (pin "2") (pinfunction "2_2") (pintype "passive"))
      (node (ref "C16") (pin "2") (pinfunction "2_2") (pintype "passive"))
      (node (ref "C17") (pin "2") (pinfunction "2_2") (pintype "passive"))
      (node (ref "X1") (pin "40") (pinfunction "VDRH_40") (pintype "passive"))
      (node (ref "X1") (pin "43") (pinfunction "VRH_43") (pintype "passive"))
      (node (ref "X1") (pin "44") (pinfunction "VTXH_44") (pintype "passive"))
      (node (ref "X6") (pin "2") (pinfunction "1_2") (pintype "passive"))
    )
    (net (code "88") (name "/VRR_FL") (class "Default")
      (node (ref "C30") (pin "2") (pinfunction "2_2") (pintype "passive"))
      (node (ref "X1") (pin "9") (pinfunction "VRR_FL_9") (pintype "passive"))
    )
    (net (code "89") (name "/VRS") (class "Default")
      (node (ref "C32") (pin "2") (pinfunction "2_2") (pintype "passive"))
      (node (ref "X1") (pin "14") (pinfunction "VRS_14") (pintype "passive"))
    )
    (net (code "90") (name "/VTZ") (class "Default")
      (node (ref "P2") (pin "4") (pinfunction "4_4") (pintype "passive"))
      (node (ref "X1") (pin "67") (pinfunction "VTZ_67") (pintype "passive"))
      (node (ref "X3") (pin "10") (pinfunction "P1.0_10") (pintype "passive"))
    )
    (net (code "91") (name "GND") (class "Default")
      (node (ref "C1") (pin "1") (pinfunction "1_1") (pintype "passive"))
      (node (ref "C10") (pin "1") (pinfunction "1_1") (pintype "passive"))
      (node (ref "C11") (pin "1") (pinfunction "1_1") (pintype "passive"))
      (node (ref "C12") (pin "1") (pinfunction "1_1") (pintype "passive"))
      (node (ref "C13") (pin "1") (pinfunction "1_1") (pintype "passive"))
      (node (ref "C14") (pin "1") (pinfunction "1_1") (pintype "passive"))
      (node (ref "C15") (pin "1") (pinfunction "1_1") (pintype "passive"))
      (node (ref "C16") (pin "1") (pinfunction "1_1") (pintype "passive"))
      (node (ref "C17") (pin "1") (pinfunction "1_1") (pintype "passive"))
      (node (ref "C18") (pin "1") (pinfunction "1_1") (pintype "passive"))
      (node (ref "C19") (pin "1") (pinfunction "1_1") (pintype "passive"))
      (node (ref "C2") (pin "1") (pinfunction "1_1") (pintype "passive"))
      (node (ref "C20") (pin "1") (pinfunction "1_1") (pintype "passive"))
      (node (ref "C21") (pin "1") (pinfunction "1_1") (pintype "passive"))
      (node (ref "C22") (pin "1") (pinfunction "1_1") (pintype "passive"))
      (node (ref "C23") (pin "1") (pinfunction "1_1") (pintype "passive"))
      (node (ref "C24") (pin "1") (pinfunction "1_1") (pintype "passive"))
      (node (ref "C25") (pin "1") (pinfunction "1_1") (pintype "passive"))
      (node (ref "C3") (pin "1") (pinfunction "1_1") (pintype "passive"))
      (node (ref "C30") (pin "1") (pinfunction "1_1") (pintype "passive"))
      (node (ref "C31") (pin "1") (pinfunction "1_1") (pintype "passive"))
      (node (ref "C32") (pin "1") (pinfunction "1_1") (pintype "passive"))
      (node (ref "C33") (pin "1") (pinfunction "1_1") (pintype "passive"))
      (node (ref "C34") (pin "1") (pinfunction "1_1") (pintype "passive"))
      (node (ref "C35") (pin "1") (pinfunction "1_1") (pintype "passive"))
      (node (ref "C36") (pin "1") (pinfunction "1_1") (pintype "passive"))
      (node (ref "C37") (pin "1") (pinfunction "1_1") (pintype "passive"))
      (node (ref "C38") (pin "1") (pinfunction "1_1") (pintype "passive"))
      (node (ref "C39") (pin "1") (pinfunction "1_1") (pintype "passive"))
      (node (ref "C4") (pin "1") (pinfunction "1_1") (pintype "passive"))
      (node (ref "C5") (pin "1") (pinfunction "1_1") (pintype "passive"))
      (node (ref "C6") (pin "1") (pinfunction "1_1") (pintype "passive"))
      (node (ref "C7") (pin "1") (pinfunction "1_1") (pintype "passive"))
      (node (ref "C8") (pin "1") (pinfunction "1_1") (pintype "passive"))
      (node (ref "C9") (pin "1") (pinfunction "1_1") (pintype "passive"))
      (node (ref "D1") (pin "12") (pinfunction "GND_12") (pintype "passive"))
      (node (ref "D1") (pin "9") (pinfunction "~{EN}_9") (pintype "passive"))
      (node (ref "D2") (pin "12") (pinfunction "GND_12") (pintype "passive"))
      (node (ref "D2") (pin "9") (pinfunction "~{EN}_9") (pintype "passive"))
      (node (ref "D3") (pin "2") (pinfunction "GND_2") (pintype "passive"))
      (node (ref "D4") (pin "12") (pinfunction "GND_12") (pintype "passive"))
      (node (ref "D4") (pin "9") (pinfunction "~{EN}_9") (pintype "passive"))
      (node (ref "LED") (pin "1") (pinfunction "1_1") (pintype "passive"))
      (node (ref "P10") (pin "1") (pinfunction "1_1") (pintype "passive"))
      (node (ref "P10") (pin "2") (pinfunction "2_2") (pintype "passive"))
      (node (ref "P3") (pin "1") (pinfunction "1_1") (pintype "passive"))
      (node (ref "P3") (pin "2") (pinfunction "2_2") (pintype "passive"))
      (node (ref "P4") (pin "1") (pinfunction "1_1") (pintype "passive"))
      (node (ref "P4") (pin "2") (pinfunction "2_2") (pintype "passive"))
      (node (ref "P5") (pin "1") (pinfunction "1_1") (pintype "passive"))
      (node (ref "P5") (pin "2") (pinfunction "2_2") (pintype "passive"))
      (node (ref "P6") (pin "1") (pinfunction "1_1") (pintype "passive"))
      (node (ref "P6") (pin "2") (pinfunction "2_2") (pintype "passive"))
      (node (ref "P7") (pin "1") (pinfunction "1_1") (pintype "passive"))
      (node (ref "P7") (pin "2") (pinfunction "2_2") (pintype "passive"))
      (node (ref "P8") (pin "1") (pinfunction "1_1") (pintype "passive"))
      (node (ref "P8") (pin "2") (pinfunction "2_2") (pintype "passive"))
      (node (ref "P9") (pin "1") (pinfunction "1_1") (pintype "passive"))
      (node (ref "P9") (pin "2") (pinfunction "2_2") (pintype "passive"))
      (node (ref "X1") (pin "21") (pinfunction "GND_21") (pintype "passive"))
      (node (ref "X1") (pin "22") (pinfunction "GND_22") (pintype "passive"))
      (node (ref "X1") (pin "23") (pinfunction "GND_23") (pintype "passive"))
      (node (ref "X1") (pin "24") (pinfunction "GND_24") (pintype "passive"))
      (node (ref "X1") (pin "25") (pinfunction "GND_25") (pintype "passive"))
      (node (ref "X1") (pin "76") (pinfunction "GND_76") (pintype "passive"))
      (node (ref "X1") (pin "86") (pinfunction "VTX2L_86") (pintype "passive"))
      (node (ref "X1") (pin "87") (pinfunction "VTX1L_87") (pintype "passive"))
      (node (ref "X1") (pin "88") (pinfunction "VRL_88") (pintype "passive"))
      (node (ref "X1") (pin "89") (pinfunction "VDRL_89") (pintype "passive"))
      (node (ref "X2") (pin "11") (pinfunction "GND_11") (pintype "passive"))
      (node (ref "X2") (pin "16") (pinfunction "GND_16") (pintype "passive"))
      (node (ref "X2") (pin "24") (pinfunction "GND_24") (pintype "passive"))
      (node (ref "X2") (pin "29") (pinfunction "GND_29") (pintype "passive"))
      (node (ref "X2") (pin "34") (pinfunction "GND_34") (pintype "passive"))
      (node (ref "X2") (pin "38") (pinfunction "GND_38") (pintype "passive"))
      (node (ref "X2") (pin "39") (pinfunction "GND_39") (pintype "passive"))
      (node (ref "X2") (pin "6") (pinfunction "GND_6") (pintype "passive"))
      (node (ref "X3") (pin "11") (pinfunction "GND_11") (pintype "passive"))
      (node (ref "X3") (pin "16") (pinfunction "GND_16") (pintype "passive"))
      (node (ref "X3") (pin "24") (pinfunction "GND_24") (pintype "passive"))
      (node (ref "X3") (pin "29") (pinfunction "GND_29") (pintype "passive"))
      (node (ref "X3") (pin "34") (pinfunction "GND_34") (pintype "passive"))
      (node (ref "X3") (pin "38") (pinfunction "GND_38") (pintype "passive"))
      (node (ref "X3") (pin "39") (pinfunction "GND_39") (pintype "passive"))
      (node (ref "X3") (pin "6") (pinfunction "GND_6") (pintype "passive"))
      (node (ref "X4") (pin "4") (pinfunction "GND_4") (pintype "passive"))
      (node (ref "X4") (pin "5") (pinfunction "GND_5") (pintype "passive"))
      (node (ref "X4") (pin "6") (pinfunction "GND_6") (pintype "passive"))
      (node (ref "X5") (pin "4") (pinfunction "GND_4") (pintype "passive"))
      (node (ref "X5") (pin "5") (pinfunction "GND_5") (pintype "passive"))
      (node (ref "X5") (pin "6") (pinfunction "GND_6") (pintype "passive"))
      (node (ref "X6") (pin "4") (pinfunction "GND_4") (pintype "passive"))
      (node (ref "X6") (pin "5") (pinfunction "GND_5") (pintype "passive"))
      (node (ref "X6") (pin "6") (pinfunction "GND_6") (pintype "passive"))
    )
    (net (code "92") (name "unconnected-(D4-RIN2_N-Pad4)") (class "Default")
      (node (ref "D4") (pin "4") (pinfunction "RIN2_N_4") (pintype "passive"))
    )
    (net (code "93") (name "unconnected-(D4-RIN2_P-Pad3)") (class "Default")
      (node (ref "D4") (pin "3") (pinfunction "RIN2_P_3") (pintype "passive"))
    )
    (net (code "94") (name "unconnected-(D4-RIN3_N-Pad5)") (class "Default")
      (node (ref "D4") (pin "5") (pinfunction "RIN3_N_5") (pintype "passive"))
    )
    (net (code "95") (name "unconnected-(D4-RIN3_P-Pad6)") (class "Default")
      (node (ref "D4") (pin "6") (pinfunction "RIN3_P_6") (pintype "passive"))
    )
    (net (code "96") (name "unconnected-(D4-RIN4_N-Pad8)") (class "Default")
      (node (ref "D4") (pin "8") (pinfunction "RIN4_N_8") (pintype "passive"))
    )
    (net (code "97") (name "unconnected-(D4-RIN4_P-Pad7)") (class "Default")
      (node (ref "D4") (pin "7") (pinfunction "RIN4_P_7") (pintype "passive"))
    )
    (net (code "98") (name "unconnected-(D4-ROUT2-Pad14)") (class "Default")
      (node (ref "D4") (pin "14") (pinfunction "ROUT2_14") (pintype "passive"))
    )
    (net (code "99") (name "unconnected-(D4-ROUT3-Pad11)") (class "Default")
      (node (ref "D4") (pin "11") (pinfunction "ROUT3_11") (pintype "passive"))
    )
    (net (code "100") (name "unconnected-(D4-ROUT4-Pad10)") (class "Default")
      (node (ref "D4") (pin "10") (pinfunction "ROUT4_10") (pintype "passive"))
    )
    (net (code "101") (name "unconnected-(X2-NC-Pad1)") (class "Default")
      (node (ref "X2") (pin "1") (pinfunction "NC_1") (pintype "passive"))
    )
    (net (code "102") (name "unconnected-(X2-NC-Pad18)") (class "Default")
      (node (ref "X2") (pin "18") (pinfunction "NC_18") (pintype "passive"))
    )
    (net (code "103") (name "unconnected-(X2-NC-Pad19)") (class "Default")
      (node (ref "X2") (pin "19") (pinfunction "NC_19") (pintype "passive"))
    )
    (net (code "104") (name "unconnected-(X2-NC-Pad37)") (class "Default")
      (node (ref "X2") (pin "37") (pinfunction "NC_37") (pintype "passive"))
    )
    (net (code "105") (name "unconnected-(X2-P2.7-Pad20)") (class "Default")
      (node (ref "X2") (pin "20") (pinfunction "P2.7_20") (pintype "passive"))
    )
    (net (code "106") (name "unconnected-(X2-PFI2-Pad17)") (class "Default")
      (node (ref "X2") (pin "17") (pinfunction "PFI2_17") (pintype "passive"))
    )
    (net (code "107") (name "unconnected-(X2-PFI3-Pad35)") (class "Default")
      (node (ref "X2") (pin "35") (pinfunction "PFI3_35") (pintype "passive"))
    )
    (net (code "108") (name "unconnected-(X3-NC-Pad1)") (class "Default")
      (node (ref "X3") (pin "1") (pinfunction "NC_1") (pintype "passive"))
    )
    (net (code "109") (name "unconnected-(X3-NC-Pad18)") (class "Default")
      (node (ref "X3") (pin "18") (pinfunction "NC_18") (pintype "passive"))
    )
    (net (code "110") (name "unconnected-(X3-NC-Pad19)") (class "Default")
      (node (ref "X3") (pin "19") (pinfunction "NC_19") (pintype "passive"))
    )
    (net (code "111") (name "unconnected-(X3-NC-Pad37)") (class "Default")
      (node (ref "X3") (pin "37") (pinfunction "NC_37") (pintype "passive"))
    )
    (net (code "112") (name "unconnected-(X3-P0.6-Pad12)") (class "Default")
      (node (ref "X3") (pin "12") (pinfunction "P0.6_12") (pintype "passive"))
    )
    (net (code "113") (name "unconnected-(X3-P2.4-Pad3)") (class "Default")
      (node (ref "X3") (pin "3") (pinfunction "P2.4_3") (pintype "passive"))
    )
    (net (code "114") (name "unconnected-(X3-P2.7-Pad20)") (class "Default")
      (node (ref "X3") (pin "20") (pinfunction "P2.7_20") (pintype "passive"))
    )
    (net (code "115") (name "unconnected-(X3-PFI2-Pad17)") (class "Default")
      (node (ref "X3") (pin "17") (pinfunction "PFI2_17") (pintype "passive"))
    )
    (net (code "116") (name "unconnected-(X3-PFI3-Pad35)") (class "Default")
      (node (ref "X3") (pin "35") (pinfunction "PFI3_35") (pintype "passive"))
    )
    (net (code "117") (name "unconnected-(X4-2-Pad3)") (class "Default")
      (node (ref "X4") (pin "3") (pinfunction "2_3") (pintype "passive"))
    )
    (net (code "118") (name "unconnected-(X5-2-Pad3)") (class "Default")
      (node (ref "X5") (pin "3") (pinfunction "2_3") (pintype "passive"))
    )
    (net (code "119") (name "unconnected-(X6-2-Pad3)") (class "Default")
      (node (ref "X6") (pin "3") (pinfunction "2_3") (pintype "passive"))
    )
    (net (code "120") (name "unconnected-(X7-+A-Pad2)") (class "Default")
      (node (ref "X7") (pin "2") (pinfunction "+A_2") (pintype "passive"))
    )
  )
)
